# Display.net
KiCad netlist of a schematic drawn in Altium Designer
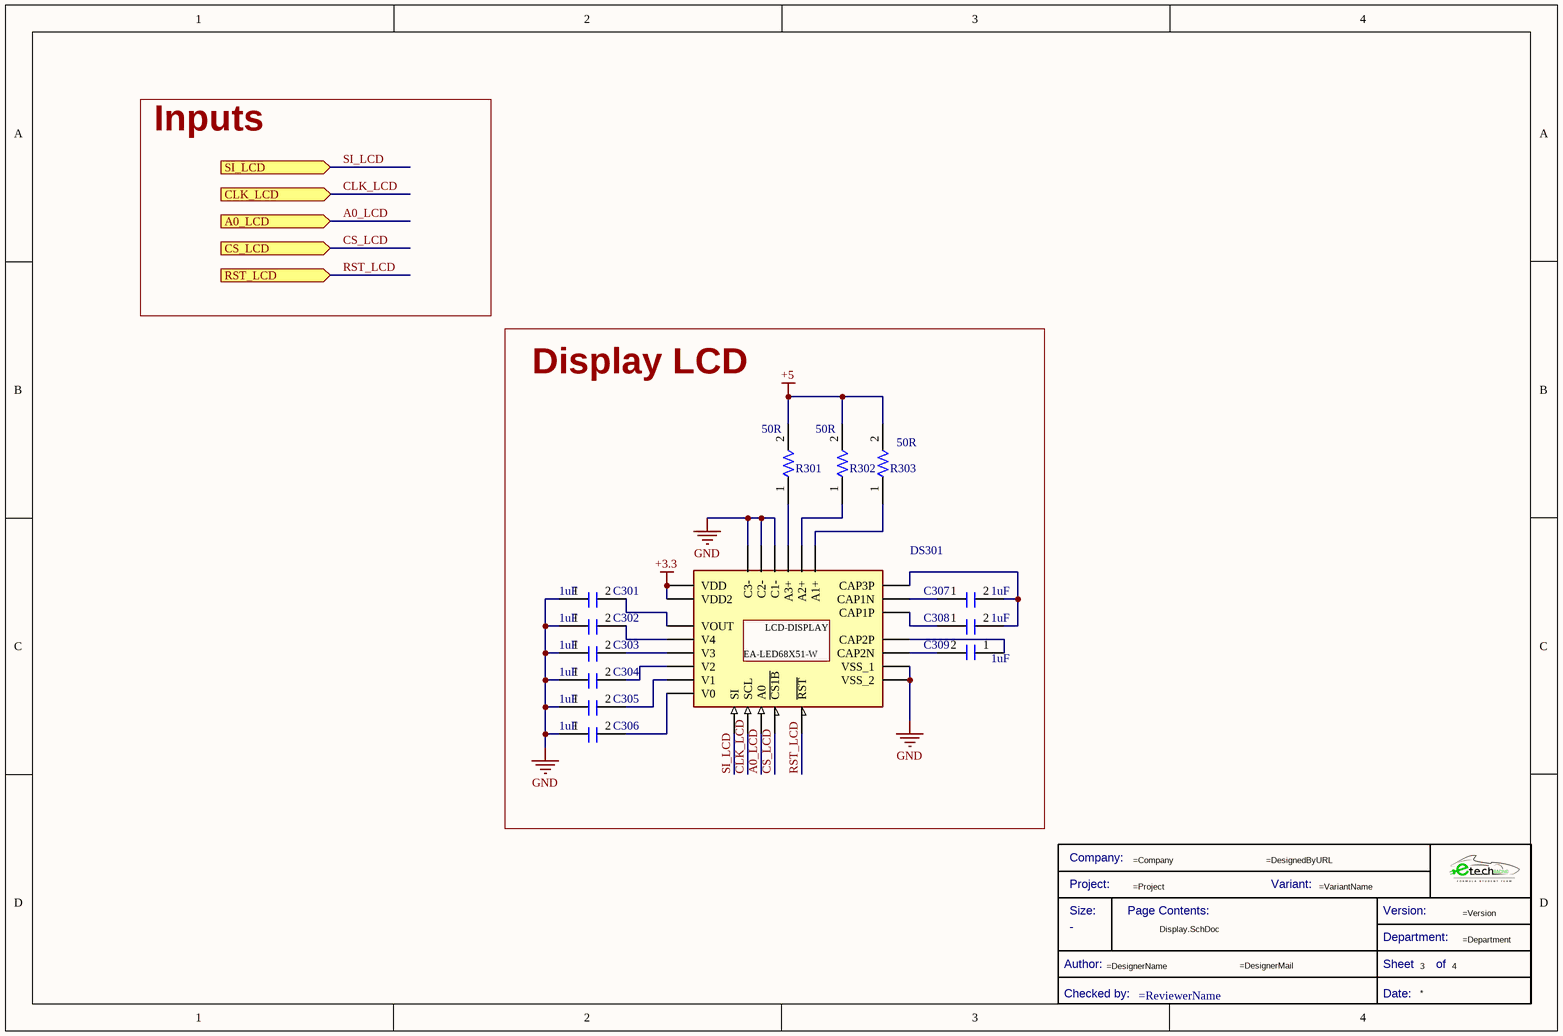
[diagram p0: Display.SchDoc]

(export (version "E")
  (design (tool "Eeschema 10.0.6"))
  (components
    (comp (ref "C301")
      (value "885012207103")
      (footprint "C0805FNPC-R")
      (fields
        (field (name "TOLERANCE") "10%")
        (field (name "CAPACITANCE") "1uF")
        (field (name ".CREATOR") "GP")
      )
      (libsource (lib "Passives") (part "C1u-50V-0805FNPC-X7R"))
    )
    (comp (ref "C302")
      (value "885012207103")
      (footprint "C0805FNPC-R")
      (fields
        (field (name "TOLERANCE") "10%")
        (field (name "CAPACITANCE") "1uF")
        (field (name ".CREATOR") "GP")
      )
      (libsource (lib "Passives") (part "C1u-50V-0805FNPC-X7R"))
    )
    (comp (ref "C303")
      (value "885012207103")
      (footprint "C0805FNPC-R")
      (fields
        (field (name "TOLERANCE") "10%")
        (field (name "CAPACITANCE") "1uF")
        (field (name ".CREATOR") "GP")
      )
      (libsource (lib "Passives") (part "C1u-50V-0805FNPC-X7R"))
    )
    (comp (ref "C304")
      (value "885012207103")
      (footprint "C0805FNPC-R")
      (fields
        (field (name "TOLERANCE") "10%")
        (field (name "CAPACITANCE") "1uF")
        (field (name ".CREATOR") "GP")
      )
      (libsource (lib "Passives") (part "C1u-50V-0805FNPC-X7R"))
    )
    (comp (ref "C305")
      (value "885012207103")
      (footprint "C0805FNPC-R")
      (fields
        (field (name "TOLERANCE") "10%")
        (field (name "CAPACITANCE") "1uF")
        (field (name ".CREATOR") "GP")
      )
      (libsource (lib "Passives") (part "C1u-50V-0805FNPC-X7R"))
    )
    (comp (ref "C306")
      (value "885012207103")
      (footprint "C0805FNPC-R")
      (fields
        (field (name "TOLERANCE") "10%")
        (field (name "CAPACITANCE") "1uF")
        (field (name ".CREATOR") "GP")
      )
      (libsource (lib "Passives") (part "C1u-50V-0805FNPC-X7R"))
    )
    (comp (ref "C307")
      (value "885012207103")
      (footprint "C0805FNPC-R")
      (fields
        (field (name "TOLERANCE") "10%")
        (field (name "CAPACITANCE") "1uF")
        (field (name ".CREATOR") "GP")
      )
      (libsource (lib "Passives") (part "C1u-50V-0805FNPC-X7R"))
    )
    (comp (ref "C308")
      (value "885012207103")
      (footprint "C0805FNPC-R")
      (fields
        (field (name "TOLERANCE") "10%")
        (field (name "CAPACITANCE") "1uF")
        (field (name ".CREATOR") "GP")
      )
      (libsource (lib "Passives") (part "C1u-50V-0805FNPC-X7R"))
    )
    (comp (ref "C309")
      (value "885012207103")
      (footprint "C0805FNPC-R")
      (fields
        (field (name "TOLERANCE") "10%")
        (field (name "CAPACITANCE") "1uF")
        (field (name ".CREATOR") "GP")
      )
      (libsource (lib "Passives") (part "C1u-50V-0805FNPC-X7R"))
    )
    (comp (ref "DS301")
      (value "EA_DOGL128W-6")
      (footprint "EA_DOGL128W-6")
      (description "LCD Graphic Display Modules & Accessories FSTN (+) Transflectv White Background")
      (fields
        (field (name "MANUFACTURER_PART_NUMBER") "EA DOGL128W-6")
        (field (name "MANUFACTURER") "Electronic Assembly")
        (field (name ".CREATOR") "GP")
      )
      (libsource (lib "Integrated circuits") (part "EA_DOGL128W-6"))
    )
    (comp (ref "R301")
      (value "50R")
      (footprint "R0805FTK")
      (description "Res Thick Film 0805 50 Ohm 1% 0.125W(1/8W) ±100ppm/C Pad SMD Automotive T/R")
      (fields
        (field (name "MANUFACTURER") "Vishay Dale")
        (field (name "MANUFACTURER PART NUMBER") "CRCW080550R0FKTA")
      )
      (libsource (lib "Passives") (part "R50-0805FTK"))
    )
    (comp (ref "R302")
      (value "50R")
      (footprint "R0805FTK")
      (description "Res Thick Film 0805 50 Ohm 1% 0.125W(1/8W) ±100ppm/C Pad SMD Automotive T/R")
      (fields
        (field (name "MANUFACTURER") "Vishay Dale")
        (field (name "MANUFACTURER PART NUMBER") "CRCW080550R0FKTA")
      )
      (libsource (lib "Passives") (part "R50-0805FTK"))
    )
    (comp (ref "R303")
      (value "50R")
      (footprint "R0805FTK")
      (description "Res Thick Film 0805 50 Ohm 1% 0.125W(1/8W) ±100ppm/C Pad SMD Automotive T/R")
      (fields
        (field (name "MANUFACTURER") "Vishay Dale")
        (field (name "MANUFACTURER PART NUMBER") "CRCW080550R0FKTA")
      )
      (libsource (lib "Passives") (part "R50-0805FTK"))
    )
  )
  (nets
    (net (code "1") (name "+3.3") (class "Default")
      (node (ref "DS301") (pin "34") (pinfunction "VDD2_34") (pintype "power_in"))
      (node (ref "DS301") (pin "35") (pinfunction "VDD_35") (pintype "power_in"))
    )
    (net (code "2") (name "+5") (class "Default")
      (node (ref "R301") (pin "2") (pinfunction "2_2") (pintype "passive"))
      (node (ref "R302") (pin "2") (pinfunction "2_2") (pintype "passive"))
      (node (ref "R303") (pin "2") (pinfunction "2_2") (pintype "passive"))
    )
    (net (code "3") (name "/A0_LCD") (class "Default")
      (node (ref "DS301") (pin "38") (pinfunction "A0_38") (pintype "input"))
    )
    (net (code "4") (name "/CLK_LCD") (class "Default")
      (node (ref "DS301") (pin "37") (pinfunction "SCL_37") (pintype "input"))
    )
    (net (code "5") (name "/CS_LCD") (class "Default")
      (node (ref "DS301") (pin "40") (pinfunction "~{CS1B}_40") (pintype "passive"))
    )
    (net (code "6") (name "/RST_LCD") (class "Default")
      (node (ref "DS301") (pin "39") (pinfunction "~{RST}_39") (pintype "passive"))
    )
    (net (code "7") (name "/SI_LCD") (class "Default")
      (node (ref "DS301") (pin "36") (pinfunction "SI_36") (pintype "input"))
    )
    (net (code "8") (name "GND") (class "Default")
      (node (ref "C301") (pin "1") (pinfunction "1_1") (pintype "passive"))
      (node (ref "C302") (pin "1") (pinfunction "1_1") (pintype "passive"))
      (node (ref "C303") (pin "1") (pinfunction "1_1") (pintype "passive"))
      (node (ref "C304") (pin "1") (pinfunction "1_1") (pintype "passive"))
      (node (ref "C305") (pin "1") (pinfunction "1_1") (pintype "passive"))
      (node (ref "C306") (pin "1") (pinfunction "1_1") (pintype "passive"))
      (node (ref "DS301") (pin "18") (pinfunction "C1-_18") (pintype "passive"))
      (node (ref "DS301") (pin "19") (pinfunction "C2-_19") (pintype "passive"))
      (node (ref "DS301") (pin "20") (pinfunction "C3-_20") (pintype "passive"))
      (node (ref "DS301") (pin "26") (pinfunction "VSS_1_26") (pintype "power_in"))
      (node (ref "DS301") (pin "33") (pinfunction "VSS_2_33") (pintype "power_in"))
    )
    (net (code "9") (name "Net-(DS301-A1+)") (class "Default")
      (node (ref "DS301") (pin "1") (pinfunction "A1+_1") (pintype "passive"))
      (node (ref "R303") (pin "1") (pinfunction "1_1") (pintype "passive"))
    )
    (net (code "10") (name "Net-(DS301-A2+)") (class "Default")
      (node (ref "DS301") (pin "2") (pinfunction "A2+_2") (pintype "passive"))
      (node (ref "R302") (pin "1") (pinfunction "1_1") (pintype "passive"))
    )
    (net (code "11") (name "Net-(DS301-A3+)") (class "Default")
      (node (ref "DS301") (pin "3") (pinfunction "A3+_3") (pintype "passive"))
      (node (ref "R301") (pin "1") (pinfunction "1_1") (pintype "passive"))
    )
    (net (code "12") (name "Net-(DS301-CAP1N)") (class "Default")
      (node (ref "C307") (pin "1") (pinfunction "1_1") (pintype "passive"))
      (node (ref "DS301") (pin "30") (pinfunction "CAP1N_30") (pintype "passive"))
    )
    (net (code "13") (name "Net-(DS301-CAP1P)") (class "Default")
      (node (ref "C308") (pin "1") (pinfunction "1_1") (pintype "passive"))
      (node (ref "DS301") (pin "29") (pinfunction "CAP1P_29") (pintype "passive"))
    )
    (net (code "14") (name "Net-(DS301-CAP2N)") (class "Default")
      (node (ref "C309") (pin "2") (pinfunction "2_2") (pintype "passive"))
      (node (ref "DS301") (pin "27") (pinfunction "CAP2N_27") (pintype "passive"))
    )
    (net (code "15") (name "Net-(DS301-CAP2P)") (class "Default")
      (node (ref "C309") (pin "1") (pinfunction "1_1") (pintype "passive"))
      (node (ref "DS301") (pin "28") (pinfunction "CAP2P_28") (pintype "passive"))
    )
    (net (code "16") (name "Net-(DS301-CAP3P)") (class "Default")
      (node (ref "C307") (pin "2") (pinfunction "2_2") (pintype "passive"))
      (node (ref "C308") (pin "2") (pinfunction "2_2") (pintype "passive"))
      (node (ref "DS301") (pin "31") (pinfunction "CAP3P_31") (pintype "passive"))
    )
    (net (code "17") (name "Net-(DS301-V0)") (class "Default")
      (node (ref "C306") (pin "2") (pinfunction "2_2") (pintype "passive"))
      (node (ref "DS301") (pin "21") (pinfunction "V0_21") (pintype "passive"))
    )
    (net (code "18") (name "Net-(DS301-V1)") (class "Default")
      (node (ref "C305") (pin "2") (pinfunction "2_2") (pintype "passive"))
      (node (ref "DS301") (pin "22") (pinfunction "V1_22") (pintype "passive"))
    )
    (net (code "19") (name "Net-(DS301-V2)") (class "Default")
      (node (ref "C304") (pin "2") (pinfunction "2_2") (pintype "passive"))
      (node (ref "DS301") (pin "23") (pinfunction "V2_23") (pintype "passive"))
    )
    (net (code "20") (name "Net-(DS301-V3)") (class "Default")
      (node (ref "C303") (pin "2") (pinfunction "2_2") (pintype "passive"))
      (node (ref "DS301") (pin "24") (pinfunction "V3_24") (pintype "passive"))
    )
    (net (code "21") (name "Net-(DS301-V4)") (class "Default")
      (node (ref "C302") (pin "2") (pinfunction "2_2") (pintype "passive"))
      (node (ref "DS301") (pin "25") (pinfunction "V4_25") (pintype "passive"))
    )
    (net (code "22") (name "Net-(DS301-VOUT)") (class "Default")
      (node (ref "C301") (pin "2") (pinfunction "2_2") (pintype "passive"))
      (node (ref "DS301") (pin "32") (pinfunction "VOUT_32") (pintype "passive"))
    )
  )
)
